# SOM_Console.net
KiCad netlist of a schematic drawn in Altium Designer
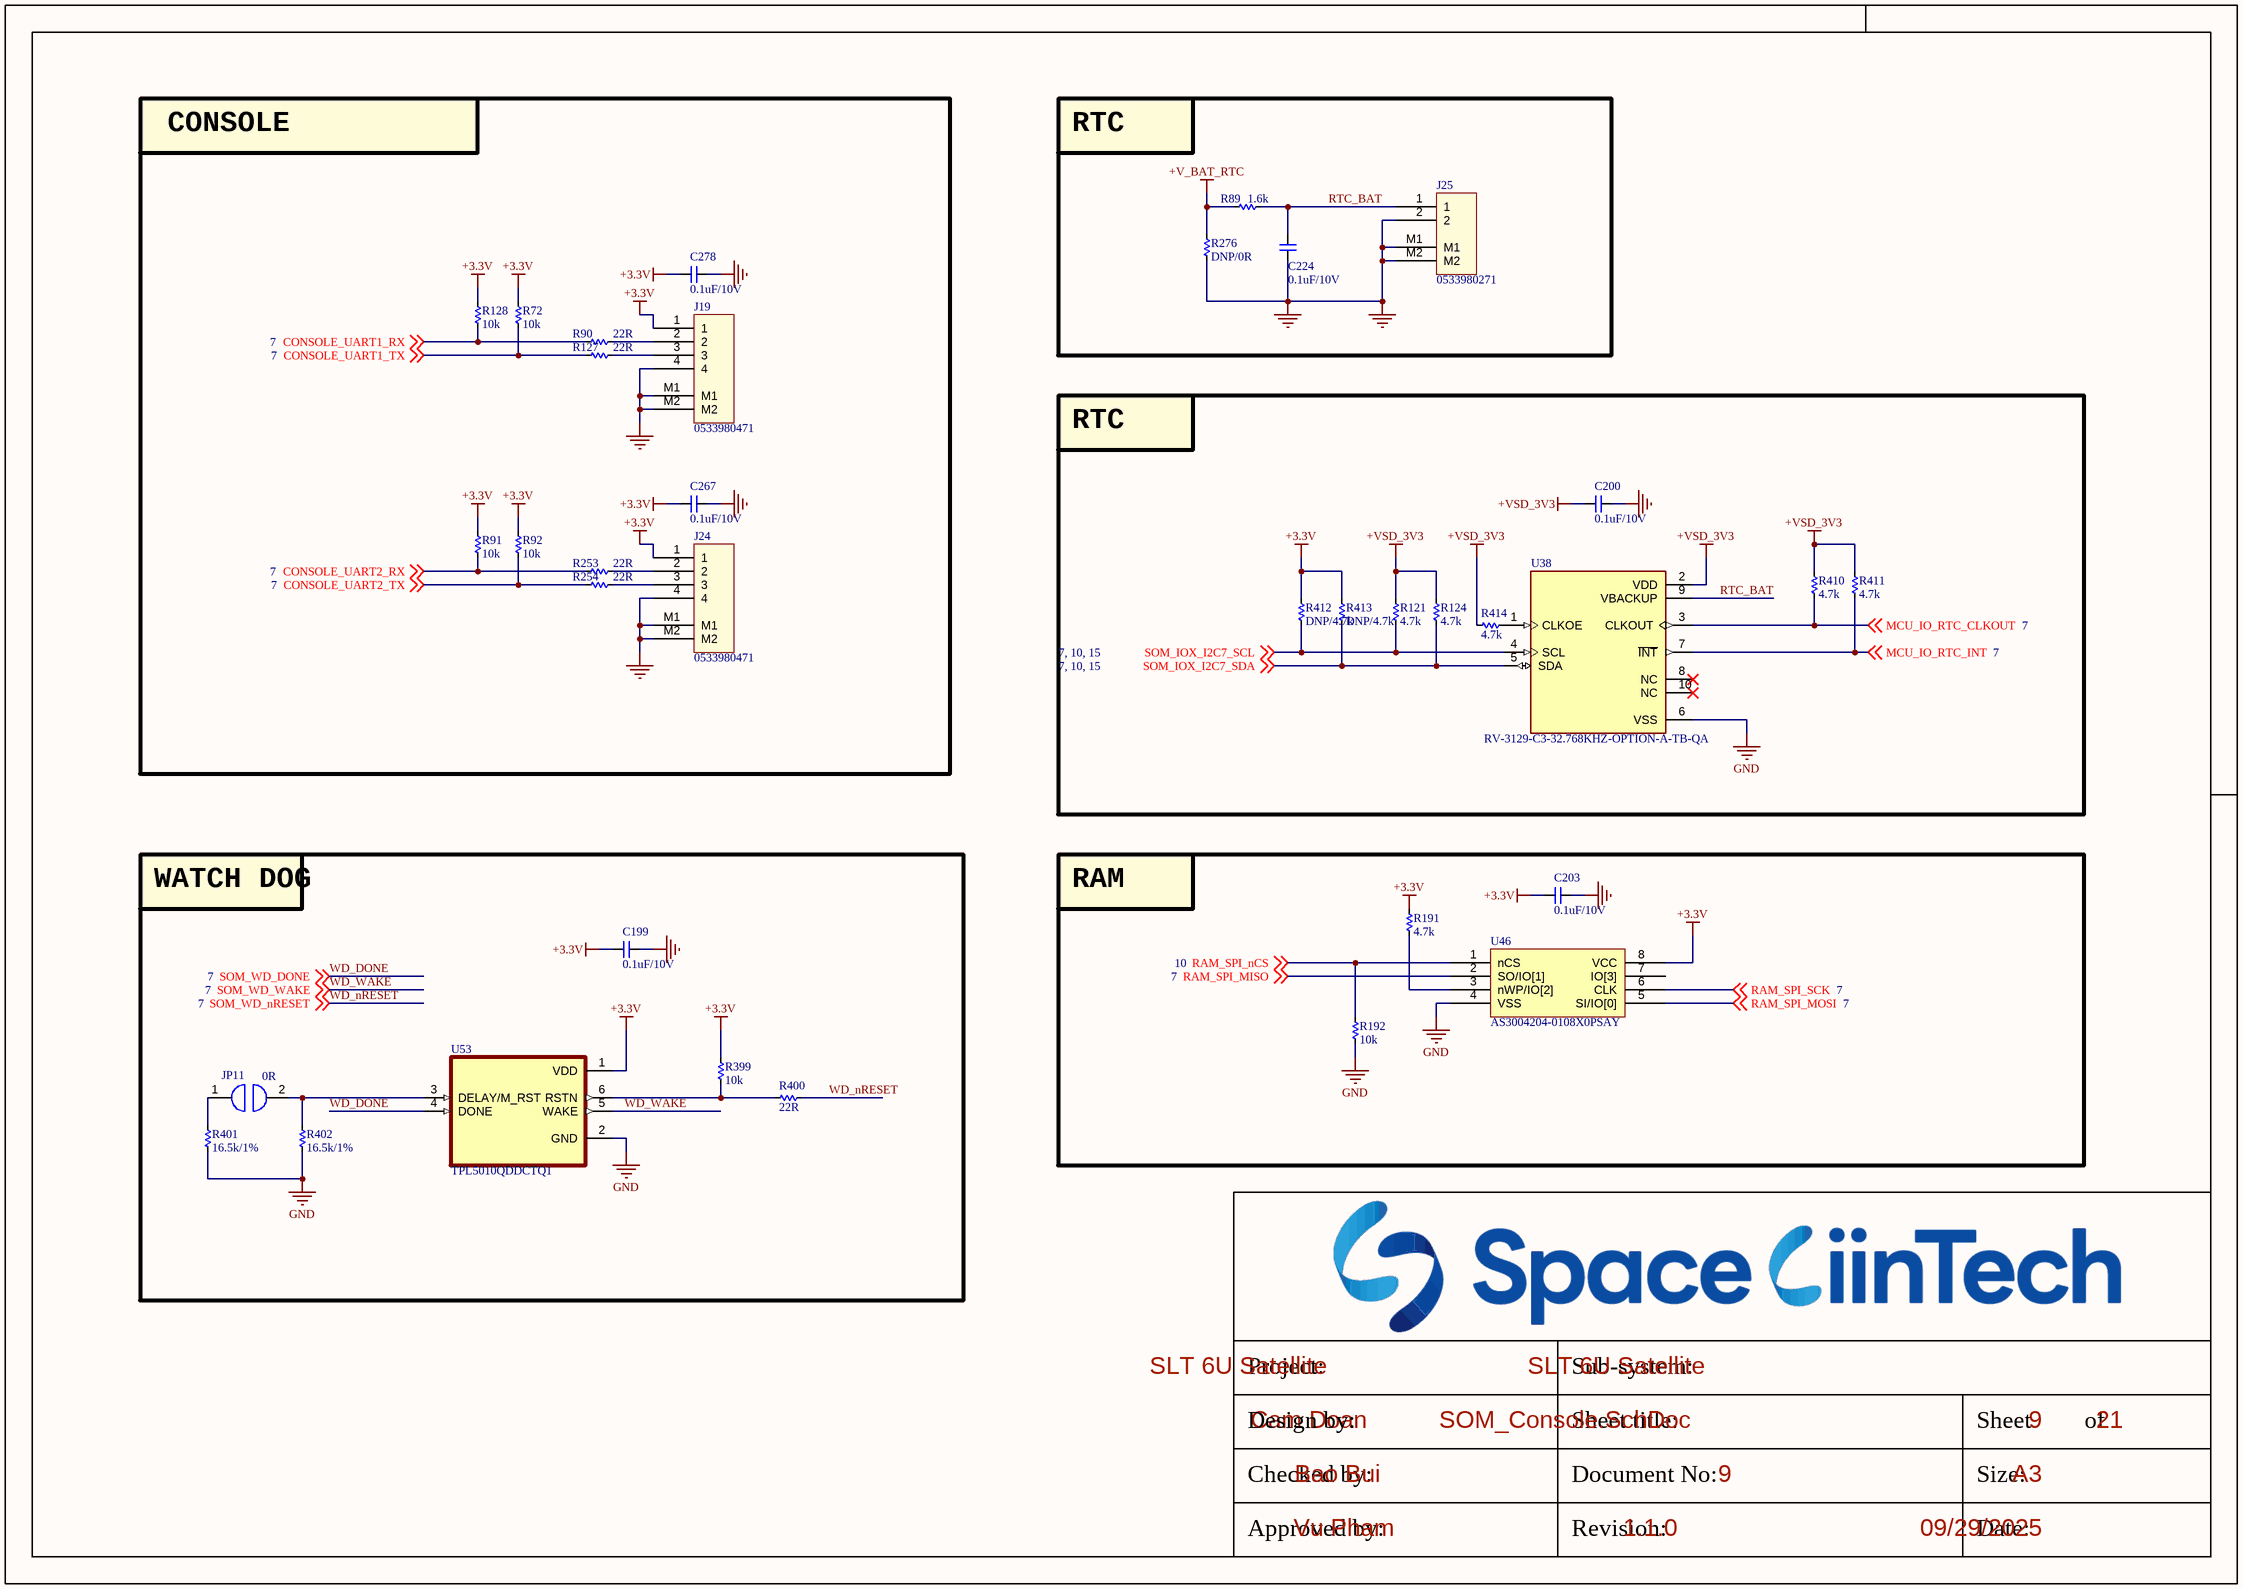
[diagram p0: SOM_Console.SchDoc]

(export (version "E")
  (design (tool "Eeschema 10.0.6"))
  (components
    (comp (ref "C199")
      (value "0.1uF/10V")
      (footprint "CAP_C_1005X60")
      (description "CAP CHIP")
      (libsource (lib "LABLIB") (part "_CAP_C_2"))
    )
    (comp (ref "C200")
      (value "0.1uF/10V")
      (footprint "CAP_C_1005X60")
      (description "CAP CHIP")
      (libsource (lib "LABLIB") (part "_CAP_C_2"))
    )
    (comp (ref "C203")
      (value "0.1uF/10V")
      (footprint "CAP_C_1005X60")
      (description "CAP CHIP")
      (libsource (lib "LABLIB") (part "_CAP_C_2"))
    )
    (comp (ref "C224")
      (value "0.1uF/10V")
      (footprint "CAP_C_1005X60")
      (description "CAP CHIP")
      (libsource (lib "LABLIB") (part "_CAP_C_2"))
    )
    (comp (ref "C267")
      (value "0.1uF/10V")
      (footprint "CAP_C_1005X60")
      (description "CAP CHIP")
      (libsource (lib "LABLIB") (part "_CAP_C_2"))
    )
    (comp (ref "C278")
      (value "0.1uF/10V")
      (footprint "CAP_C_1005X60")
      (description "CAP CHIP")
      (libsource (lib "LABLIB") (part "_CAP_C_2"))
    )
    (comp (ref "J19")
      (value "0533980471")
      (footprint "MOLEX_0533980471")
      (libsource (lib "LABLIB") (part "Header 4x1_2M"))
    )
    (comp (ref "J24")
      (value "0533980471")
      (footprint "MOLEX_0533980471")
      (libsource (lib "LABLIB") (part "Header 4x1_2M"))
    )
    (comp (ref "J25")
      (value "0533980271")
      (footprint "MOLEX_0533980271")
      (libsource (lib "LABLIB") (part "Header 2x1_2M"))
    )
    (comp (ref "JP11") (value "0R") (footprint "RES_C_1608X60") (libsource (lib "EXP_V1") (part "JUMPER")))
    (comp (ref "R72")
      (value "10k")
      (footprint "RES_C_1005X40")
      (description "RES")
      (libsource (lib "LABLIB") (part "_RES_B_2"))
    )
    (comp (ref "R89")
      (value "1.6k")
      (footprint "RES_C_1005X40")
      (description "RES")
      (libsource (lib "LABLIB") (part "_RES_B_2"))
    )
    (comp (ref "R90")
      (value "22R")
      (footprint "RES_C_1005X40")
      (description "RES")
      (libsource (lib "LABLIB") (part "_RES_B_2"))
    )
    (comp (ref "R91")
      (value "10k")
      (footprint "RES_C_1005X40")
      (description "RES")
      (libsource (lib "LABLIB") (part "_RES_B_2"))
    )
    (comp (ref "R92")
      (value "10k")
      (footprint "RES_C_1005X40")
      (description "RES")
      (libsource (lib "LABLIB") (part "_RES_B_2"))
    )
    (comp (ref "R121")
      (value "4.7k")
      (footprint "RES_C_1005X40")
      (description "RES")
      (libsource (lib "LABLIB") (part "_RES_B_2"))
    )
    (comp (ref "R124")
      (value "4.7k")
      (footprint "RES_C_1005X40")
      (description "RES")
      (libsource (lib "LABLIB") (part "_RES_B_2"))
    )
    (comp (ref "R127")
      (value "22R")
      (footprint "RES_C_1005X40")
      (description "RES")
      (libsource (lib "LABLIB") (part "_RES_B_2"))
    )
    (comp (ref "R128")
      (value "10k")
      (footprint "RES_C_1005X40")
      (description "RES")
      (libsource (lib "LABLIB") (part "_RES_B_2"))
    )
    (comp (ref "R191")
      (value "4.7k")
      (footprint "RES_C_1005X40")
      (description "RES")
      (libsource (lib "LABLIB") (part "_RES_B_2"))
    )
    (comp (ref "R192")
      (value "10k")
      (footprint "RES_C_1005X40")
      (description "RES")
      (libsource (lib "LABLIB") (part "_RES_B_2"))
    )
    (comp (ref "R253")
      (value "22R")
      (footprint "RES_C_1005X40")
      (description "RES")
      (libsource (lib "LABLIB") (part "_RES_B_2"))
    )
    (comp (ref "R254")
      (value "22R")
      (footprint "RES_C_1005X40")
      (description "RES")
      (libsource (lib "LABLIB") (part "_RES_B_2"))
    )
    (comp (ref "R276")
      (value "DNP/0R")
      (footprint "RES_C_1005X40")
      (description "RES")
      (libsource (lib "LABLIB") (part "_RES_B_2"))
    )
    (comp (ref "R399")
      (value "10k")
      (footprint "RES_C_1005X40")
      (description "RES")
      (libsource (lib "LABLIB") (part "_RES_B_2"))
    )
    (comp (ref "R400")
      (value "22R")
      (footprint "RES_C_1005X40")
      (description "RES")
      (libsource (lib "LABLIB") (part "_RES_B_2"))
    )
    (comp (ref "R401")
      (value "16.5k/1%")
      (footprint "RES_C_1005X40")
      (description "RES")
      (libsource (lib "LABLIB") (part "_RES_B_2"))
    )
    (comp (ref "R402")
      (value "16.5k/1%")
      (footprint "RES_C_1005X40")
      (description "RES")
      (libsource (lib "LABLIB") (part "_RES_B_2"))
    )
    (comp (ref "R410")
      (value "4.7k")
      (footprint "RES_C_1005X40")
      (description "RES")
      (libsource (lib "LABLIB") (part "_RES_B_2"))
    )
    (comp (ref "R411")
      (value "4.7k")
      (footprint "RES_C_1005X40")
      (description "RES")
      (libsource (lib "LABLIB") (part "_RES_B_2"))
    )
    (comp (ref "R412")
      (value "DNP/4.7k")
      (footprint "RES_C_1005X40")
      (description "RES")
      (libsource (lib "LABLIB") (part "_RES_B_2"))
    )
    (comp (ref "R413")
      (value "DNP/4.7k")
      (footprint "RES_C_1005X40")
      (description "RES")
      (libsource (lib "LABLIB") (part "_RES_B_2"))
    )
    (comp (ref "R414")
      (value "4.7k")
      (footprint "RES_C_1005X40")
      (description "RES")
      (libsource (lib "LABLIB") (part "_RES_B_2"))
    )
    (comp (ref "U38")
      (value "RV-3129-C3-32.768KHZ-OPTION-A-TB-QA")
      (footprint "IC_RV-3129-C3_32.768KHZ_OPTION_A_TB_QA")
      (description "Real-Time Clock Module, Temperature compensated, in 2.5 x 3.7 mm package")
      (fields (field (name "MF") "Micro Crystal") (field (name "MP") "RV-3129-C3 32.768KHZ OPTION A TB QA"))
      (libsource (lib "RV-3129-C3_32.768KHZ_OPTION_A_TB_QA") (part "RV-3129-C3_32.768KHZ_OPTION_A_TB_QA"))
    )
    (comp (ref "U46")
      (value "AS3004204-0108X0PSAY")
      (footprint "SOIC127P790X216-8")
      (libsource (lib "LABLIB") (part "IC_RAM_AS3004204-0108X0PSAY"))
    )
    (comp (ref "U53")
      (value "TPL5010QDDCTQ1")
      (footprint "SOT95P280X145-6N")
      (libsource (lib "TPL5010QDDCTQ1") (part "TPL5010QDDCTQ1"))
    )
  )
  (nets
    (net (code "1") (name "+3.3V") (class "Default")
      (node (ref "C199") (pin "2") (pinfunction "2_2") (pintype "passive"))
      (node (ref "C203") (pin "2") (pinfunction "2_2") (pintype "passive"))
      (node (ref "C267") (pin "2") (pinfunction "2_2") (pintype "passive"))
      (node (ref "C278") (pin "2") (pinfunction "2_2") (pintype "passive"))
      (node (ref "J19") (pin "1") (pinfunction "1_1") (pintype "passive"))
      (node (ref "J24") (pin "1") (pinfunction "1_1") (pintype "passive"))
      (node (ref "R128") (pin "2") (pinfunction "2_2") (pintype "passive"))
      (node (ref "R191") (pin "2") (pinfunction "2_2") (pintype "passive"))
      (node (ref "R399") (pin "2") (pinfunction "2_2") (pintype "passive"))
      (node (ref "R412") (pin "2") (pinfunction "2_2") (pintype "passive"))
      (node (ref "R413") (pin "2") (pinfunction "2_2") (pintype "passive"))
      (node (ref "R72") (pin "2") (pinfunction "2_2") (pintype "passive"))
      (node (ref "R91") (pin "2") (pinfunction "2_2") (pintype "passive"))
      (node (ref "R92") (pin "2") (pinfunction "2_2") (pintype "passive"))
      (node (ref "U46") (pin "8") (pinfunction "VCC_8") (pintype "passive"))
      (node (ref "U53") (pin "1") (pinfunction "VDD_1") (pintype "power_in"))
    )
    (net (code "2") (name "+VSD_3V3") (class "Default")
      (node (ref "C200") (pin "2") (pinfunction "2_2") (pintype "passive"))
      (node (ref "R121") (pin "2") (pinfunction "2_2") (pintype "passive"))
      (node (ref "R124") (pin "2") (pinfunction "2_2") (pintype "passive"))
      (node (ref "R410") (pin "2") (pinfunction "2_2") (pintype "passive"))
      (node (ref "R411") (pin "2") (pinfunction "2_2") (pintype "passive"))
      (node (ref "R414") (pin "2") (pinfunction "2_2") (pintype "passive"))
      (node (ref "U38") (pin "2") (pinfunction "VDD_2") (pintype "power_in"))
    )
    (net (code "3") (name "+V_BAT_RTC") (class "Default")
      (node (ref "R276") (pin "1") (pinfunction "1_1") (pintype "passive"))
      (node (ref "R89") (pin "1") (pinfunction "1_1") (pintype "passive"))
    )
    (net (code "4") (name "/RTC_BAT") (class "Default")
      (node (ref "C224") (pin "2") (pinfunction "2_2") (pintype "passive"))
      (node (ref "J25") (pin "1") (pinfunction "1_1") (pintype "passive"))
      (node (ref "R89") (pin "2") (pinfunction "2_2") (pintype "passive"))
      (node (ref "U38") (pin "9") (pinfunction "VBACKUP_9") (pintype "power_in"))
    )
    (net (code "5") (name "CONSOLE_UART1_RX") (class "Default")
      (node (ref "R128") (pin "1") (pinfunction "1_1") (pintype "passive"))
      (node (ref "R90") (pin "2") (pinfunction "2_2") (pintype "passive"))
    )
    (net (code "6") (name "CONSOLE_UART1_TX") (class "Default")
      (node (ref "R127") (pin "2") (pinfunction "2_2") (pintype "passive"))
      (node (ref "R72") (pin "1") (pinfunction "1_1") (pintype "passive"))
    )
    (net (code "7") (name "CONSOLE_UART2_RX") (class "Default")
      (node (ref "R253") (pin "2") (pinfunction "2_2") (pintype "passive"))
      (node (ref "R91") (pin "1") (pinfunction "1_1") (pintype "passive"))
    )
    (net (code "8") (name "CONSOLE_UART2_TX") (class "Default")
      (node (ref "R254") (pin "2") (pinfunction "2_2") (pintype "passive"))
      (node (ref "R92") (pin "1") (pinfunction "1_1") (pintype "passive"))
    )
    (net (code "9") (name "GND") (class "Default")
      (node (ref "C199") (pin "1") (pinfunction "1_1") (pintype "passive"))
      (node (ref "C200") (pin "1") (pinfunction "1_1") (pintype "passive"))
      (node (ref "C203") (pin "1") (pinfunction "1_1") (pintype "passive"))
      (node (ref "C224") (pin "1") (pinfunction "1_1") (pintype "passive"))
      (node (ref "C267") (pin "1") (pinfunction "1_1") (pintype "passive"))
      (node (ref "C278") (pin "1") (pinfunction "1_1") (pintype "passive"))
      (node (ref "J19") (pin "4") (pinfunction "4_4") (pintype "passive"))
      (node (ref "J19") (pin "M1") (pinfunction "M1_M1") (pintype "passive"))
      (node (ref "J19") (pin "M2") (pinfunction "M2_M2") (pintype "passive"))
      (node (ref "J24") (pin "4") (pinfunction "4_4") (pintype "passive"))
      (node (ref "J24") (pin "M1") (pinfunction "M1_M1") (pintype "passive"))
      (node (ref "J24") (pin "M2") (pinfunction "M2_M2") (pintype "passive"))
      (node (ref "J25") (pin "2") (pinfunction "2_2") (pintype "passive"))
      (node (ref "J25") (pin "M1") (pinfunction "M1_M1") (pintype "passive"))
      (node (ref "J25") (pin "M2") (pinfunction "M2_M2") (pintype "passive"))
      (node (ref "R192") (pin "1") (pinfunction "1_1") (pintype "passive"))
      (node (ref "R276") (pin "2") (pinfunction "2_2") (pintype "passive"))
      (node (ref "R401") (pin "1") (pinfunction "1_1") (pintype "passive"))
      (node (ref "R402") (pin "1") (pinfunction "1_1") (pintype "passive"))
      (node (ref "U38") (pin "6") (pinfunction "VSS_6") (pintype "power_in"))
      (node (ref "U46") (pin "4") (pinfunction "VSS_4") (pintype "passive"))
      (node (ref "U53") (pin "2") (pinfunction "GND_2") (pintype "power_in"))
    )
    (net (code "10") (name "MCU_IO_RTC_CLKOUT") (class "Default")
      (node (ref "R410") (pin "1") (pinfunction "1_1") (pintype "passive"))
      (node (ref "U38") (pin "3") (pinfunction "CLKOUT_3") (pintype "output"))
    )
    (net (code "11") (name "MCU_IO_RTC_INT") (class "Default")
      (node (ref "R411") (pin "1") (pinfunction "1_1") (pintype "passive"))
      (node (ref "U38") (pin "7") (pinfunction "~{INT}_7") (pintype "output"))
    )
    (net (code "12") (name "Net-(J19-Pad2)") (class "Default")
      (node (ref "J19") (pin "2") (pinfunction "2_2") (pintype "passive"))
      (node (ref "R90") (pin "1") (pinfunction "1_1") (pintype "passive"))
    )
    (net (code "13") (name "Net-(J19-Pad3)") (class "Default")
      (node (ref "J19") (pin "3") (pinfunction "3_3") (pintype "passive"))
      (node (ref "R127") (pin "1") (pinfunction "1_1") (pintype "passive"))
    )
    (net (code "14") (name "Net-(J24-Pad2)") (class "Default")
      (node (ref "J24") (pin "2") (pinfunction "2_2") (pintype "passive"))
      (node (ref "R253") (pin "1") (pinfunction "1_1") (pintype "passive"))
    )
    (net (code "15") (name "Net-(J24-Pad3)") (class "Default")
      (node (ref "J24") (pin "3") (pinfunction "3_3") (pintype "passive"))
      (node (ref "R254") (pin "1") (pinfunction "1_1") (pintype "passive"))
    )
    (net (code "16") (name "Net-(JP11-Pad1)") (class "Default")
      (node (ref "JP11") (pin "1") (pinfunction "1_1") (pintype "passive"))
      (node (ref "R401") (pin "2") (pinfunction "2_2") (pintype "passive"))
    )
    (net (code "17") (name "Net-(U38-CLKOE)") (class "Default")
      (node (ref "R414") (pin "1") (pinfunction "1_1") (pintype "passive"))
      (node (ref "U38") (pin "1") (pinfunction "CLKOE_1") (pintype "input"))
    )
    (net (code "18") (name "Net-(U46-nWP{slash}IO[2])") (class "Default")
      (node (ref "R191") (pin "1") (pinfunction "1_1") (pintype "passive"))
      (node (ref "U46") (pin "3") (pinfunction "nWP/IO[2]_3") (pintype "passive"))
    )
    (net (code "19") (name "Net-(U53-DELAY{slash}M_RST)") (class "Default")
      (node (ref "JP11") (pin "2") (pinfunction "2_2") (pintype "passive"))
      (node (ref "R402") (pin "2") (pinfunction "2_2") (pintype "passive"))
      (node (ref "U53") (pin "3") (pinfunction "DELAY/M_RST_3") (pintype "input"))
    )
    (net (code "20") (name "Net-(U53-RSTN)") (class "Default")
      (node (ref "R399") (pin "1") (pinfunction "1_1") (pintype "passive"))
      (node (ref "R400") (pin "2") (pinfunction "2_2") (pintype "passive"))
      (node (ref "U53") (pin "6") (pinfunction "RSTN_6") (pintype "output"))
    )
    (net (code "21") (name "RAM_SPI_MISO") (class "Default")
      (node (ref "U46") (pin "2") (pinfunction "SO/IO[1]_2") (pintype "passive"))
    )
    (net (code "22") (name "RAM_SPI_MOSI") (class "Default")
      (node (ref "U46") (pin "5") (pinfunction "SI/IO[0]_5") (pintype "passive"))
    )
    (net (code "23") (name "RAM_SPI_SCK") (class "Default")
      (node (ref "U46") (pin "6") (pinfunction "CLK_6") (pintype "passive"))
    )
    (net (code "24") (name "RAM_SPI_nCS") (class "Default")
      (node (ref "R192") (pin "2") (pinfunction "2_2") (pintype "passive"))
      (node (ref "U46") (pin "1") (pinfunction "nCS_1") (pintype "passive"))
    )
    (net (code "25") (name "SOM_IOX_I2C7_SCL") (class "Default")
      (node (ref "R121") (pin "1") (pinfunction "1_1") (pintype "passive"))
      (node (ref "R412") (pin "1") (pinfunction "1_1") (pintype "passive"))
      (node (ref "U38") (pin "4") (pinfunction "SCL_4") (pintype "input"))
    )
    (net (code "26") (name "SOM_IOX_I2C7_SDA") (class "Default")
      (node (ref "R124") (pin "1") (pinfunction "1_1") (pintype "passive"))
      (node (ref "R413") (pin "1") (pinfunction "1_1") (pintype "passive"))
      (node (ref "U38") (pin "5") (pinfunction "SDA_5") (pintype "bidirectional"))
    )
    (net (code "27") (name "SOM_WD_DONE") (class "Default")
      (node (ref "U53") (pin "4") (pinfunction "DONE_4") (pintype "input"))
    )
    (net (code "28") (name "SOM_WD_WAKE") (class "Default")
      (node (ref "U53") (pin "5") (pinfunction "WAKE_5") (pintype "output"))
    )
    (net (code "29") (name "SOM_WD_nRESET") (class "Default")
      (node (ref "R400") (pin "1") (pinfunction "1_1") (pintype "passive"))
    )
    (net (code "30") (name "unconnected-(U38-NC-Pad8)") (class "Default")
      (node (ref "U38") (pin "8") (pinfunction "NC_8") (pintype "passive+no_connect"))
    )
    (net (code "31") (name "unconnected-(U38-NC-Pad10)") (class "Default")
      (node (ref "U38") (pin "10") (pinfunction "NC_10") (pintype "passive+no_connect"))
    )
    (net (code "32") (name "unconnected-(U46-IO[3]-Pad7)") (class "Default")
      (node (ref "U46") (pin "7") (pinfunction "IO[3]_7") (pintype "passive"))
    )
  )
)
